# Filter3.net
KiCad netlist of a schematic drawn in Altium Designer
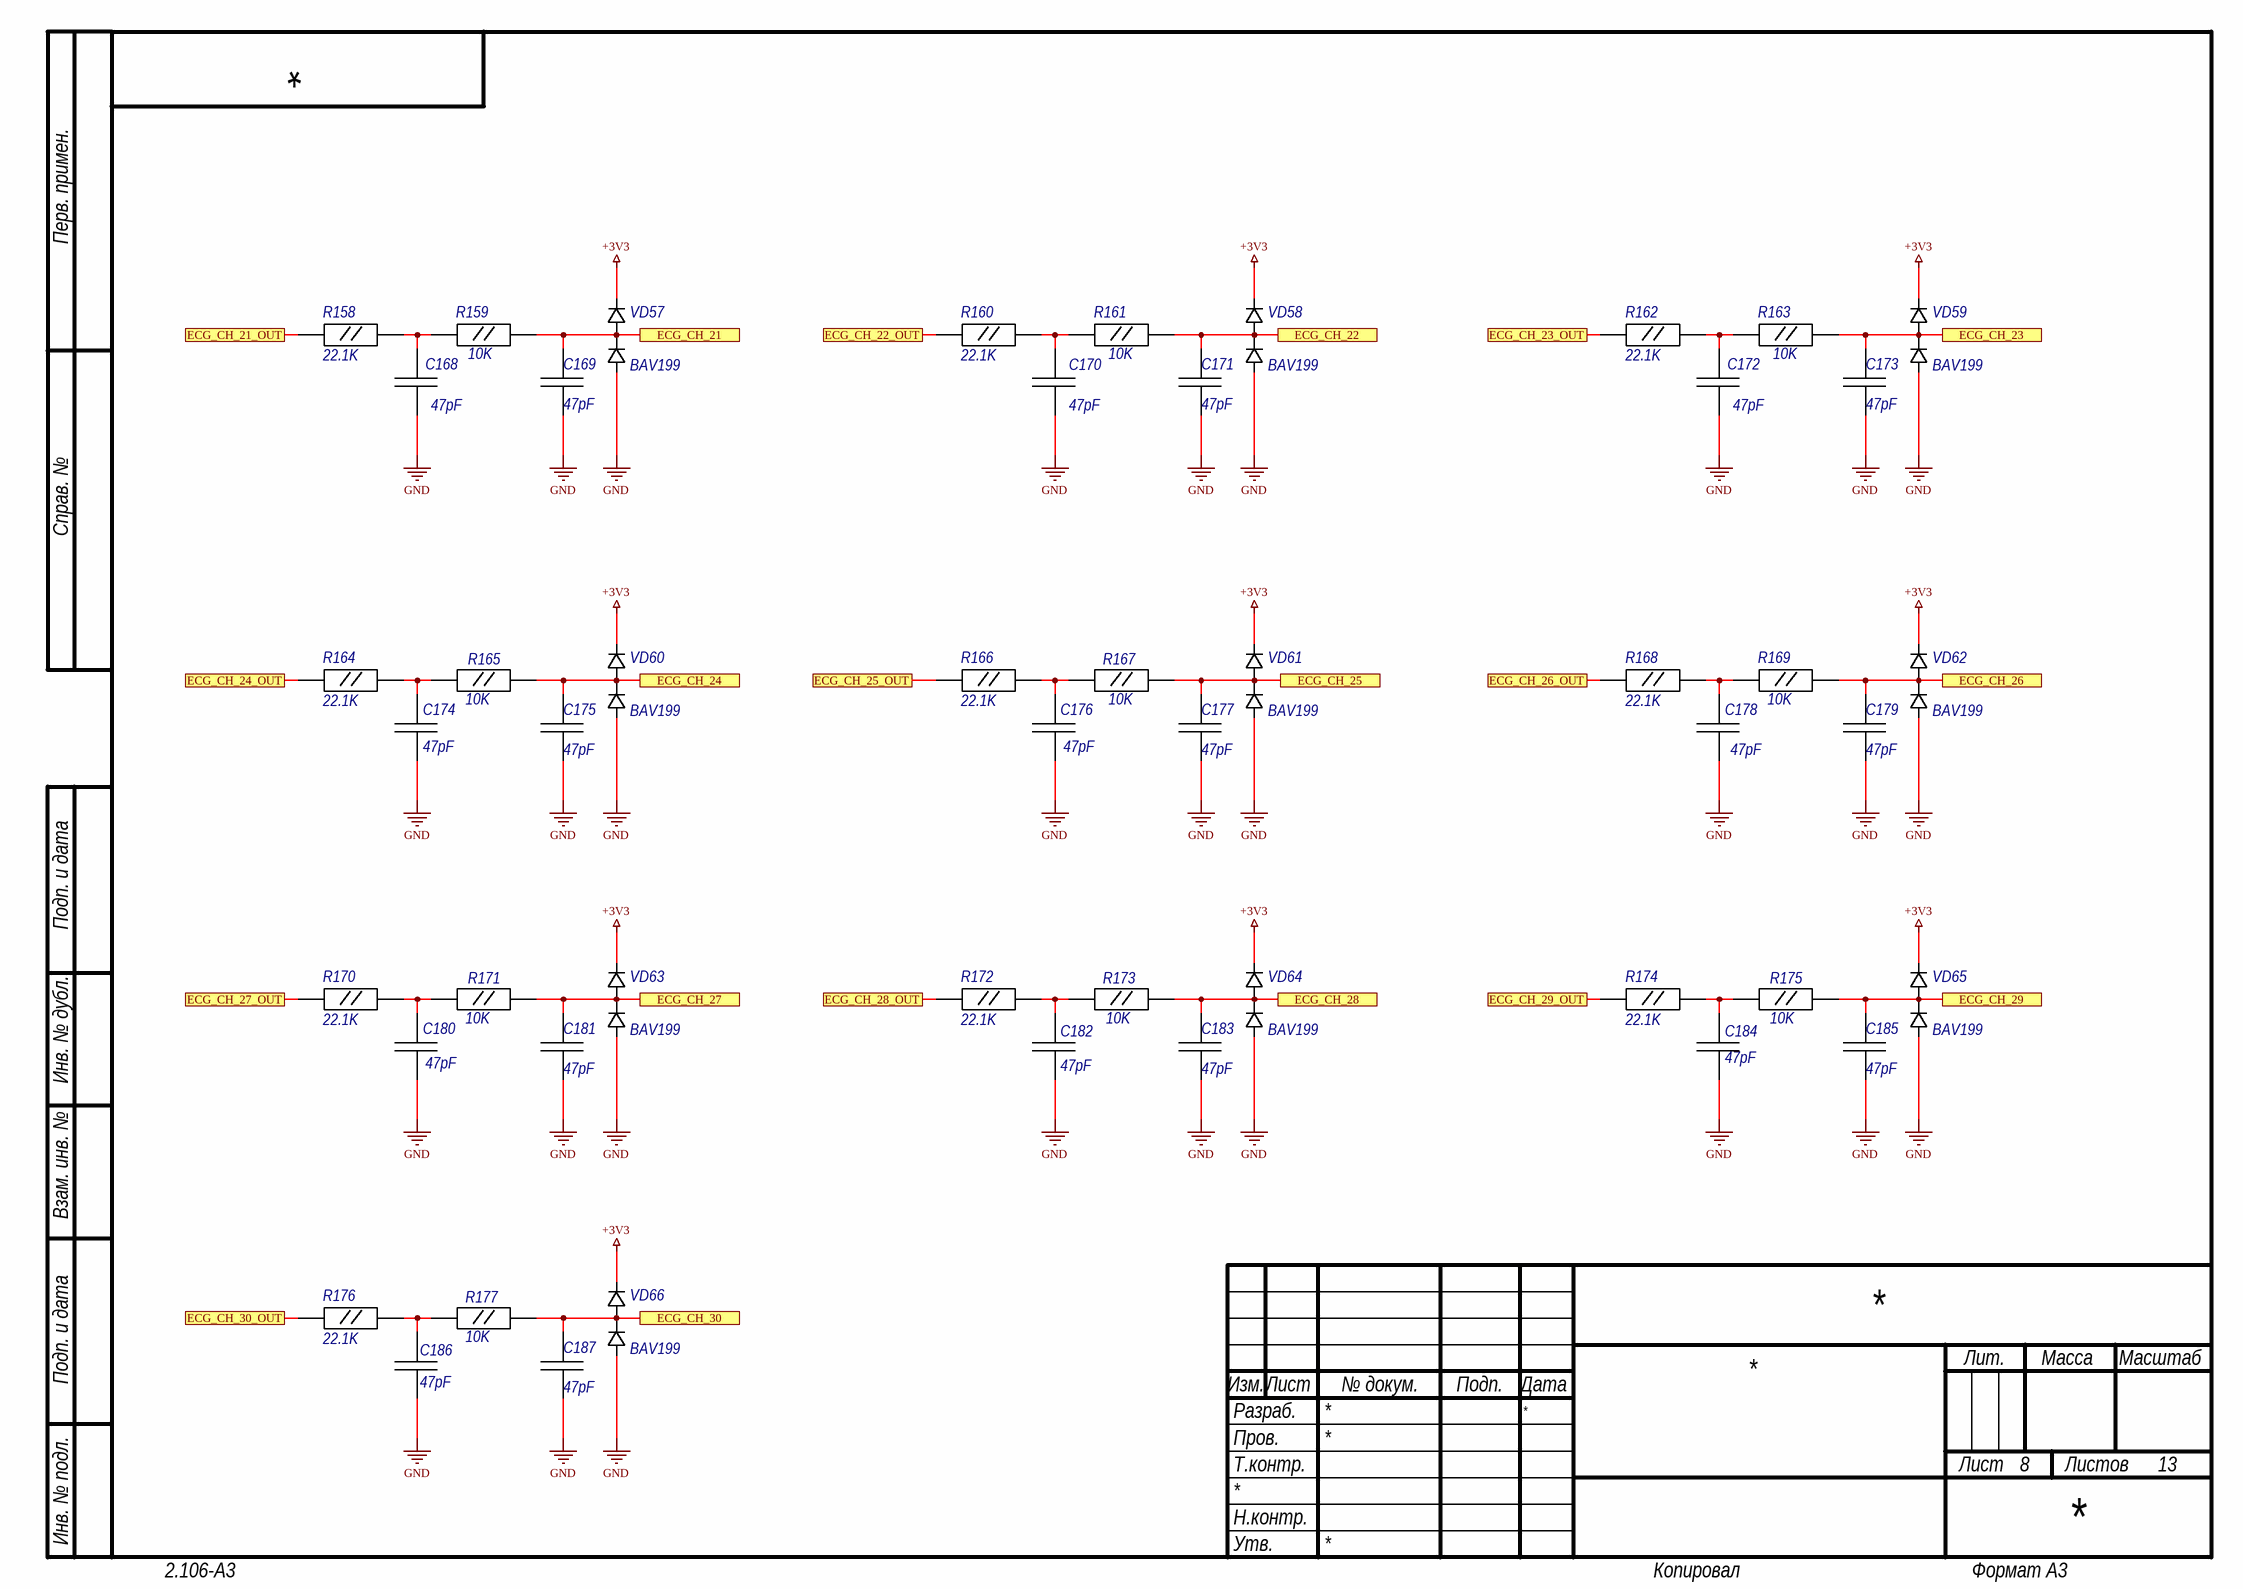
[diagram p0: Filter3.SchDoc]

(export (version "E")
  (design (tool "Eeschema 10.0.6"))
  (components
    (comp (ref "C168")
      (value "47pF")
      (footprint "C0603")
      (description "Ceramic Capacitor SMD")
      (libsource (lib "GOST") (part "CC_SMD_0603"))
    )
    (comp (ref "C169")
      (value "47pF")
      (footprint "C0603")
      (description "Ceramic Capacitor SMD")
      (libsource (lib "GOST") (part "CC_SMD_0603"))
    )
    (comp (ref "C170")
      (value "47pF")
      (footprint "C0603")
      (description "Ceramic Capacitor SMD")
      (libsource (lib "GOST") (part "CC_SMD_0603"))
    )
    (comp (ref "C171")
      (value "47pF")
      (footprint "C0603")
      (description "Ceramic Capacitor SMD")
      (libsource (lib "GOST") (part "CC_SMD_0603"))
    )
    (comp (ref "C172")
      (value "47pF")
      (footprint "C0603")
      (description "Ceramic Capacitor SMD")
      (libsource (lib "GOST") (part "CC_SMD_0603"))
    )
    (comp (ref "C173")
      (value "47pF")
      (footprint "C0603")
      (description "Ceramic Capacitor SMD")
      (libsource (lib "GOST") (part "CC_SMD_0603"))
    )
    (comp (ref "C174")
      (value "47pF")
      (footprint "C0603")
      (description "Ceramic Capacitor SMD")
      (libsource (lib "GOST") (part "CC_SMD_0603"))
    )
    (comp (ref "C175")
      (value "47pF")
      (footprint "C0603")
      (description "Ceramic Capacitor SMD")
      (libsource (lib "GOST") (part "CC_SMD_0603"))
    )
    (comp (ref "C176")
      (value "47pF")
      (footprint "C0603")
      (description "Ceramic Capacitor SMD")
      (libsource (lib "GOST") (part "CC_SMD_0603"))
    )
    (comp (ref "C177")
      (value "47pF")
      (footprint "C0603")
      (description "Ceramic Capacitor SMD")
      (libsource (lib "GOST") (part "CC_SMD_0603"))
    )
    (comp (ref "C178")
      (value "47pF")
      (footprint "C0603")
      (description "Ceramic Capacitor SMD")
      (libsource (lib "GOST") (part "CC_SMD_0603"))
    )
    (comp (ref "C179")
      (value "47pF")
      (footprint "C0603")
      (description "Ceramic Capacitor SMD")
      (libsource (lib "GOST") (part "CC_SMD_0603"))
    )
    (comp (ref "C180")
      (value "47pF")
      (footprint "C0603")
      (description "Ceramic Capacitor SMD")
      (libsource (lib "GOST") (part "CC_SMD_0603"))
    )
    (comp (ref "C181")
      (value "47pF")
      (footprint "C0603")
      (description "Ceramic Capacitor SMD")
      (libsource (lib "GOST") (part "CC_SMD_0603"))
    )
    (comp (ref "C182")
      (value "47pF")
      (footprint "C0603")
      (description "Ceramic Capacitor SMD")
      (libsource (lib "GOST") (part "CC_SMD_0603"))
    )
    (comp (ref "C183")
      (value "47pF")
      (footprint "C0603")
      (description "Ceramic Capacitor SMD")
      (libsource (lib "GOST") (part "CC_SMD_0603"))
    )
    (comp (ref "C184")
      (value "47pF")
      (footprint "C0603")
      (description "Ceramic Capacitor SMD")
      (libsource (lib "GOST") (part "CC_SMD_0603"))
    )
    (comp (ref "C185")
      (value "47pF")
      (footprint "C0603")
      (description "Ceramic Capacitor SMD")
      (libsource (lib "GOST") (part "CC_SMD_0603"))
    )
    (comp (ref "C186")
      (value "47pF")
      (footprint "C0603")
      (description "Ceramic Capacitor SMD")
      (libsource (lib "GOST") (part "CC_SMD_0603"))
    )
    (comp (ref "C187")
      (value "47pF")
      (footprint "C0603")
      (description "Ceramic Capacitor SMD")
      (libsource (lib "GOST") (part "CC_SMD_0603"))
    )
    (comp (ref "R158")
      (value "22.1K")
      (footprint "R0603")
      (description "Resistor SMD")
      (libsource (lib "GOST") (part "R0603"))
    )
    (comp (ref "R159")
      (value "10K")
      (footprint "R0603")
      (description "Resistor SMD")
      (libsource (lib "GOST") (part "R0603"))
    )
    (comp (ref "R160")
      (value "22.1K")
      (footprint "R0603")
      (description "Resistor SMD")
      (libsource (lib "GOST") (part "R0603"))
    )
    (comp (ref "R161")
      (value "10K")
      (footprint "R0603")
      (description "Resistor SMD")
      (libsource (lib "GOST") (part "R0603"))
    )
    (comp (ref "R162")
      (value "22.1K")
      (footprint "R0603")
      (description "Resistor SMD")
      (libsource (lib "GOST") (part "R0603"))
    )
    (comp (ref "R163")
      (value "10K")
      (footprint "R0603")
      (description "Resistor SMD")
      (libsource (lib "GOST") (part "R0603"))
    )
    (comp (ref "R164")
      (value "22.1K")
      (footprint "R0603")
      (description "Resistor SMD")
      (libsource (lib "GOST") (part "R0603"))
    )
    (comp (ref "R165")
      (value "10K")
      (footprint "R0603")
      (description "Resistor SMD")
      (libsource (lib "GOST") (part "R0603"))
    )
    (comp (ref "R166")
      (value "22.1K")
      (footprint "R0603")
      (description "Resistor SMD")
      (libsource (lib "GOST") (part "R0603"))
    )
    (comp (ref "R167")
      (value "10K")
      (footprint "R0603")
      (description "Resistor SMD")
      (libsource (lib "GOST") (part "R0603"))
    )
    (comp (ref "R168")
      (value "22.1K")
      (footprint "R0603")
      (description "Resistor SMD")
      (libsource (lib "GOST") (part "R0603"))
    )
    (comp (ref "R169")
      (value "10K")
      (footprint "R0603")
      (description "Resistor SMD")
      (libsource (lib "GOST") (part "R0603"))
    )
    (comp (ref "R170")
      (value "22.1K")
      (footprint "R0603")
      (description "Resistor SMD")
      (libsource (lib "GOST") (part "R0603"))
    )
    (comp (ref "R171")
      (value "10K")
      (footprint "R0603")
      (description "Resistor SMD")
      (libsource (lib "GOST") (part "R0603"))
    )
    (comp (ref "R172")
      (value "22.1K")
      (footprint "R0603")
      (description "Resistor SMD")
      (libsource (lib "GOST") (part "R0603"))
    )
    (comp (ref "R173")
      (value "10K")
      (footprint "R0603")
      (description "Resistor SMD")
      (libsource (lib "GOST") (part "R0603"))
    )
    (comp (ref "R174")
      (value "22.1K")
      (footprint "R0603")
      (description "Resistor SMD")
      (libsource (lib "GOST") (part "R0603"))
    )
    (comp (ref "R175")
      (value "10K")
      (footprint "R0603")
      (description "Resistor SMD")
      (libsource (lib "GOST") (part "R0603"))
    )
    (comp (ref "R176")
      (value "22.1K")
      (footprint "R0603")
      (description "Resistor SMD")
      (libsource (lib "GOST") (part "R0603"))
    )
    (comp (ref "R177")
      (value "10K")
      (footprint "R0603")
      (description "Resistor SMD")
      (libsource (lib "GOST") (part "R0603"))
    )
    (comp (ref "VD57")
      (value "BAV199")
      (footprint "SOT23")
      (description "Diod Schottky")
      (fields (field (name "MANUFACTURER PART NUMBER 1") "BAV199"))
      (libsource (lib "GOST") (part "DIODE_BAV199"))
    )
    (comp (ref "VD58")
      (value "BAV199")
      (footprint "SOT23")
      (description "Diod Schottky")
      (fields (field (name "MANUFACTURER PART NUMBER 1") "BAV199"))
      (libsource (lib "GOST") (part "DIODE_BAV199"))
    )
    (comp (ref "VD59")
      (value "BAV199")
      (footprint "SOT23")
      (description "Diod Schottky")
      (fields (field (name "MANUFACTURER PART NUMBER 1") "BAV199"))
      (libsource (lib "GOST") (part "DIODE_BAV199"))
    )
    (comp (ref "VD60")
      (value "BAV199")
      (footprint "SOT23")
      (description "Diod Schottky")
      (fields (field (name "MANUFACTURER PART NUMBER 1") "BAV199"))
      (libsource (lib "GOST") (part "DIODE_BAV199"))
    )
    (comp (ref "VD61")
      (value "BAV199")
      (footprint "SOT23")
      (description "Diod Schottky")
      (fields (field (name "MANUFACTURER PART NUMBER 1") "BAV199"))
      (libsource (lib "GOST") (part "DIODE_BAV199"))
    )
    (comp (ref "VD62")
      (value "BAV199")
      (footprint "SOT23")
      (description "Diod Schottky")
      (fields (field (name "MANUFACTURER PART NUMBER 1") "BAV199"))
      (libsource (lib "GOST") (part "DIODE_BAV199"))
    )
    (comp (ref "VD63")
      (value "BAV199")
      (footprint "SOT23")
      (description "Diod Schottky")
      (fields (field (name "MANUFACTURER PART NUMBER 1") "BAV199"))
      (libsource (lib "GOST") (part "DIODE_BAV199"))
    )
    (comp (ref "VD64")
      (value "BAV199")
      (footprint "SOT23")
      (description "Diod Schottky")
      (fields (field (name "MANUFACTURER PART NUMBER 1") "BAV199"))
      (libsource (lib "GOST") (part "DIODE_BAV199"))
    )
    (comp (ref "VD65")
      (value "BAV199")
      (footprint "SOT23")
      (description "Diod Schottky")
      (fields (field (name "MANUFACTURER PART NUMBER 1") "BAV199"))
      (libsource (lib "GOST") (part "DIODE_BAV199"))
    )
    (comp (ref "VD66")
      (value "BAV199")
      (footprint "SOT23")
      (description "Diod Schottky")
      (fields (field (name "MANUFACTURER PART NUMBER 1") "BAV199"))
      (libsource (lib "GOST") (part "DIODE_BAV199"))
    )
  )
  (nets
    (net (code "1") (name "+3V3") (class "Default")
      (node (ref "VD57") (pin "2") (pinfunction "2_2") (pintype "passive"))
      (node (ref "VD58") (pin "2") (pinfunction "2_2") (pintype "passive"))
      (node (ref "VD59") (pin "2") (pinfunction "2_2") (pintype "passive"))
      (node (ref "VD60") (pin "2") (pinfunction "2_2") (pintype "passive"))
      (node (ref "VD61") (pin "2") (pinfunction "2_2") (pintype "passive"))
      (node (ref "VD62") (pin "2") (pinfunction "2_2") (pintype "passive"))
      (node (ref "VD63") (pin "2") (pinfunction "2_2") (pintype "passive"))
      (node (ref "VD64") (pin "2") (pinfunction "2_2") (pintype "passive"))
      (node (ref "VD65") (pin "2") (pinfunction "2_2") (pintype "passive"))
      (node (ref "VD66") (pin "2") (pinfunction "2_2") (pintype "passive"))
    )
    (net (code "2") (name "/ECG_CH_21") (class "Default")
      (node (ref "C169") (pin "2") (pinfunction "2_2") (pintype "passive"))
      (node (ref "R159") (pin "2") (pinfunction "2_2") (pintype "passive"))
      (node (ref "VD57") (pin "3") (pinfunction "3_3") (pintype "passive"))
    )
    (net (code "3") (name "/ECG_CH_21_OUT") (class "Default")
      (node (ref "R158") (pin "1") (pinfunction "1_1") (pintype "passive"))
    )
    (net (code "4") (name "/ECG_CH_22") (class "Default")
      (node (ref "C171") (pin "2") (pinfunction "2_2") (pintype "passive"))
      (node (ref "R161") (pin "2") (pinfunction "2_2") (pintype "passive"))
      (node (ref "VD58") (pin "3") (pinfunction "3_3") (pintype "passive"))
    )
    (net (code "5") (name "/ECG_CH_22_OUT") (class "Default")
      (node (ref "R160") (pin "1") (pinfunction "1_1") (pintype "passive"))
    )
    (net (code "6") (name "/ECG_CH_23") (class "Default")
      (node (ref "C173") (pin "2") (pinfunction "2_2") (pintype "passive"))
      (node (ref "R163") (pin "2") (pinfunction "2_2") (pintype "passive"))
      (node (ref "VD59") (pin "3") (pinfunction "3_3") (pintype "passive"))
    )
    (net (code "7") (name "/ECG_CH_23_OUT") (class "Default")
      (node (ref "R162") (pin "1") (pinfunction "1_1") (pintype "passive"))
    )
    (net (code "8") (name "/ECG_CH_24") (class "Default")
      (node (ref "C175") (pin "2") (pinfunction "2_2") (pintype "passive"))
      (node (ref "R165") (pin "2") (pinfunction "2_2") (pintype "passive"))
      (node (ref "VD60") (pin "3") (pinfunction "3_3") (pintype "passive"))
    )
    (net (code "9") (name "/ECG_CH_24_OUT") (class "Default")
      (node (ref "R164") (pin "1") (pinfunction "1_1") (pintype "passive"))
    )
    (net (code "10") (name "/ECG_CH_25") (class "Default")
      (node (ref "C177") (pin "2") (pinfunction "2_2") (pintype "passive"))
      (node (ref "R167") (pin "2") (pinfunction "2_2") (pintype "passive"))
      (node (ref "VD61") (pin "3") (pinfunction "3_3") (pintype "passive"))
    )
    (net (code "11") (name "/ECG_CH_25_OUT") (class "Default")
      (node (ref "R166") (pin "1") (pinfunction "1_1") (pintype "passive"))
    )
    (net (code "12") (name "/ECG_CH_26") (class "Default")
      (node (ref "C179") (pin "2") (pinfunction "2_2") (pintype "passive"))
      (node (ref "R169") (pin "2") (pinfunction "2_2") (pintype "passive"))
      (node (ref "VD62") (pin "3") (pinfunction "3_3") (pintype "passive"))
    )
    (net (code "13") (name "/ECG_CH_26_OUT") (class "Default")
      (node (ref "R168") (pin "1") (pinfunction "1_1") (pintype "passive"))
    )
    (net (code "14") (name "/ECG_CH_27") (class "Default")
      (node (ref "C181") (pin "2") (pinfunction "2_2") (pintype "passive"))
      (node (ref "R171") (pin "2") (pinfunction "2_2") (pintype "passive"))
      (node (ref "VD63") (pin "3") (pinfunction "3_3") (pintype "passive"))
    )
    (net (code "15") (name "/ECG_CH_27_OUT") (class "Default")
      (node (ref "R170") (pin "1") (pinfunction "1_1") (pintype "passive"))
    )
    (net (code "16") (name "/ECG_CH_28") (class "Default")
      (node (ref "C183") (pin "2") (pinfunction "2_2") (pintype "passive"))
      (node (ref "R173") (pin "2") (pinfunction "2_2") (pintype "passive"))
      (node (ref "VD64") (pin "3") (pinfunction "3_3") (pintype "passive"))
    )
    (net (code "17") (name "/ECG_CH_28_OUT") (class "Default")
      (node (ref "R172") (pin "1") (pinfunction "1_1") (pintype "passive"))
    )
    (net (code "18") (name "/ECG_CH_29") (class "Default")
      (node (ref "C185") (pin "2") (pinfunction "2_2") (pintype "passive"))
      (node (ref "R175") (pin "2") (pinfunction "2_2") (pintype "passive"))
      (node (ref "VD65") (pin "3") (pinfunction "3_3") (pintype "passive"))
    )
    (net (code "19") (name "/ECG_CH_29_OUT") (class "Default")
      (node (ref "R174") (pin "1") (pinfunction "1_1") (pintype "passive"))
    )
    (net (code "20") (name "/ECG_CH_30") (class "Default")
      (node (ref "C187") (pin "2") (pinfunction "2_2") (pintype "passive"))
      (node (ref "R177") (pin "2") (pinfunction "2_2") (pintype "passive"))
      (node (ref "VD66") (pin "3") (pinfunction "3_3") (pintype "passive"))
    )
    (net (code "21") (name "/ECG_CH_30_OUT") (class "Default")
      (node (ref "R176") (pin "1") (pinfunction "1_1") (pintype "passive"))
    )
    (net (code "22") (name "GND") (class "Default")
      (node (ref "C168") (pin "1") (pinfunction "1_1") (pintype "passive"))
      (node (ref "C169") (pin "1") (pinfunction "1_1") (pintype "passive"))
      (node (ref "C170") (pin "1") (pinfunction "1_1") (pintype "passive"))
      (node (ref "C171") (pin "1") (pinfunction "1_1") (pintype "passive"))
      (node (ref "C172") (pin "1") (pinfunction "1_1") (pintype "passive"))
      (node (ref "C173") (pin "1") (pinfunction "1_1") (pintype "passive"))
      (node (ref "C174") (pin "1") (pinfunction "1_1") (pintype "passive"))
      (node (ref "C175") (pin "1") (pinfunction "1_1") (pintype "passive"))
      (node (ref "C176") (pin "1") (pinfunction "1_1") (pintype "passive"))
      (node (ref "C177") (pin "1") (pinfunction "1_1") (pintype "passive"))
      (node (ref "C178") (pin "1") (pinfunction "1_1") (pintype "passive"))
      (node (ref "C179") (pin "1") (pinfunction "1_1") (pintype "passive"))
      (node (ref "C180") (pin "1") (pinfunction "1_1") (pintype "passive"))
      (node (ref "C181") (pin "1") (pinfunction "1_1") (pintype "passive"))
      (node (ref "C182") (pin "1") (pinfunction "1_1") (pintype "passive"))
      (node (ref "C183") (pin "1") (pinfunction "1_1") (pintype "passive"))
      (node (ref "C184") (pin "1") (pinfunction "1_1") (pintype "passive"))
      (node (ref "C185") (pin "1") (pinfunction "1_1") (pintype "passive"))
      (node (ref "C186") (pin "1") (pinfunction "1_1") (pintype "passive"))
      (node (ref "C187") (pin "1") (pinfunction "1_1") (pintype "passive"))
      (node (ref "VD57") (pin "1") (pinfunction "1_1") (pintype "passive"))
      (node (ref "VD58") (pin "1") (pinfunction "1_1") (pintype "passive"))
      (node (ref "VD59") (pin "1") (pinfunction "1_1") (pintype "passive"))
      (node (ref "VD60") (pin "1") (pinfunction "1_1") (pintype "passive"))
      (node (ref "VD61") (pin "1") (pinfunction "1_1") (pintype "passive"))
      (node (ref "VD62") (pin "1") (pinfunction "1_1") (pintype "passive"))
      (node (ref "VD63") (pin "1") (pinfunction "1_1") (pintype "passive"))
      (node (ref "VD64") (pin "1") (pinfunction "1_1") (pintype "passive"))
      (node (ref "VD65") (pin "1") (pinfunction "1_1") (pintype "passive"))
      (node (ref "VD66") (pin "1") (pinfunction "1_1") (pintype "passive"))
    )
    (net (code "23") (name "Net-(C168-Pad2)") (class "Default")
      (node (ref "C168") (pin "2") (pinfunction "2_2") (pintype "passive"))
      (node (ref "R158") (pin "2") (pinfunction "2_2") (pintype "passive"))
      (node (ref "R159") (pin "1") (pinfunction "1_1") (pintype "passive"))
    )
    (net (code "24") (name "Net-(C170-Pad2)") (class "Default")
      (node (ref "C170") (pin "2") (pinfunction "2_2") (pintype "passive"))
      (node (ref "R160") (pin "2") (pinfunction "2_2") (pintype "passive"))
      (node (ref "R161") (pin "1") (pinfunction "1_1") (pintype "passive"))
    )
    (net (code "25") (name "Net-(C172-Pad2)") (class "Default")
      (node (ref "C172") (pin "2") (pinfunction "2_2") (pintype "passive"))
      (node (ref "R162") (pin "2") (pinfunction "2_2") (pintype "passive"))
      (node (ref "R163") (pin "1") (pinfunction "1_1") (pintype "passive"))
    )
    (net (code "26") (name "Net-(C174-Pad2)") (class "Default")
      (node (ref "C174") (pin "2") (pinfunction "2_2") (pintype "passive"))
      (node (ref "R164") (pin "2") (pinfunction "2_2") (pintype "passive"))
      (node (ref "R165") (pin "1") (pinfunction "1_1") (pintype "passive"))
    )
    (net (code "27") (name "Net-(C176-Pad2)") (class "Default")
      (node (ref "C176") (pin "2") (pinfunction "2_2") (pintype "passive"))
      (node (ref "R166") (pin "2") (pinfunction "2_2") (pintype "passive"))
      (node (ref "R167") (pin "1") (pinfunction "1_1") (pintype "passive"))
    )
    (net (code "28") (name "Net-(C178-Pad2)") (class "Default")
      (node (ref "C178") (pin "2") (pinfunction "2_2") (pintype "passive"))
      (node (ref "R168") (pin "2") (pinfunction "2_2") (pintype "passive"))
      (node (ref "R169") (pin "1") (pinfunction "1_1") (pintype "passive"))
    )
    (net (code "29") (name "Net-(C180-Pad2)") (class "Default")
      (node (ref "C180") (pin "2") (pinfunction "2_2") (pintype "passive"))
      (node (ref "R170") (pin "2") (pinfunction "2_2") (pintype "passive"))
      (node (ref "R171") (pin "1") (pinfunction "1_1") (pintype "passive"))
    )
    (net (code "30") (name "Net-(C182-Pad2)") (class "Default")
      (node (ref "C182") (pin "2") (pinfunction "2_2") (pintype "passive"))
      (node (ref "R172") (pin "2") (pinfunction "2_2") (pintype "passive"))
      (node (ref "R173") (pin "1") (pinfunction "1_1") (pintype "passive"))
    )
    (net (code "31") (name "Net-(C184-Pad2)") (class "Default")
      (node (ref "C184") (pin "2") (pinfunction "2_2") (pintype "passive"))
      (node (ref "R174") (pin "2") (pinfunction "2_2") (pintype "passive"))
      (node (ref "R175") (pin "1") (pinfunction "1_1") (pintype "passive"))
    )
    (net (code "32") (name "Net-(C186-Pad2)") (class "Default")
      (node (ref "C186") (pin "2") (pinfunction "2_2") (pintype "passive"))
      (node (ref "R176") (pin "2") (pinfunction "2_2") (pintype "passive"))
      (node (ref "R177") (pin "1") (pinfunction "1_1") (pintype "passive"))
    )
  )
)
